# Sheet1.net
KiCad netlist of a schematic drawn in Altium Designer
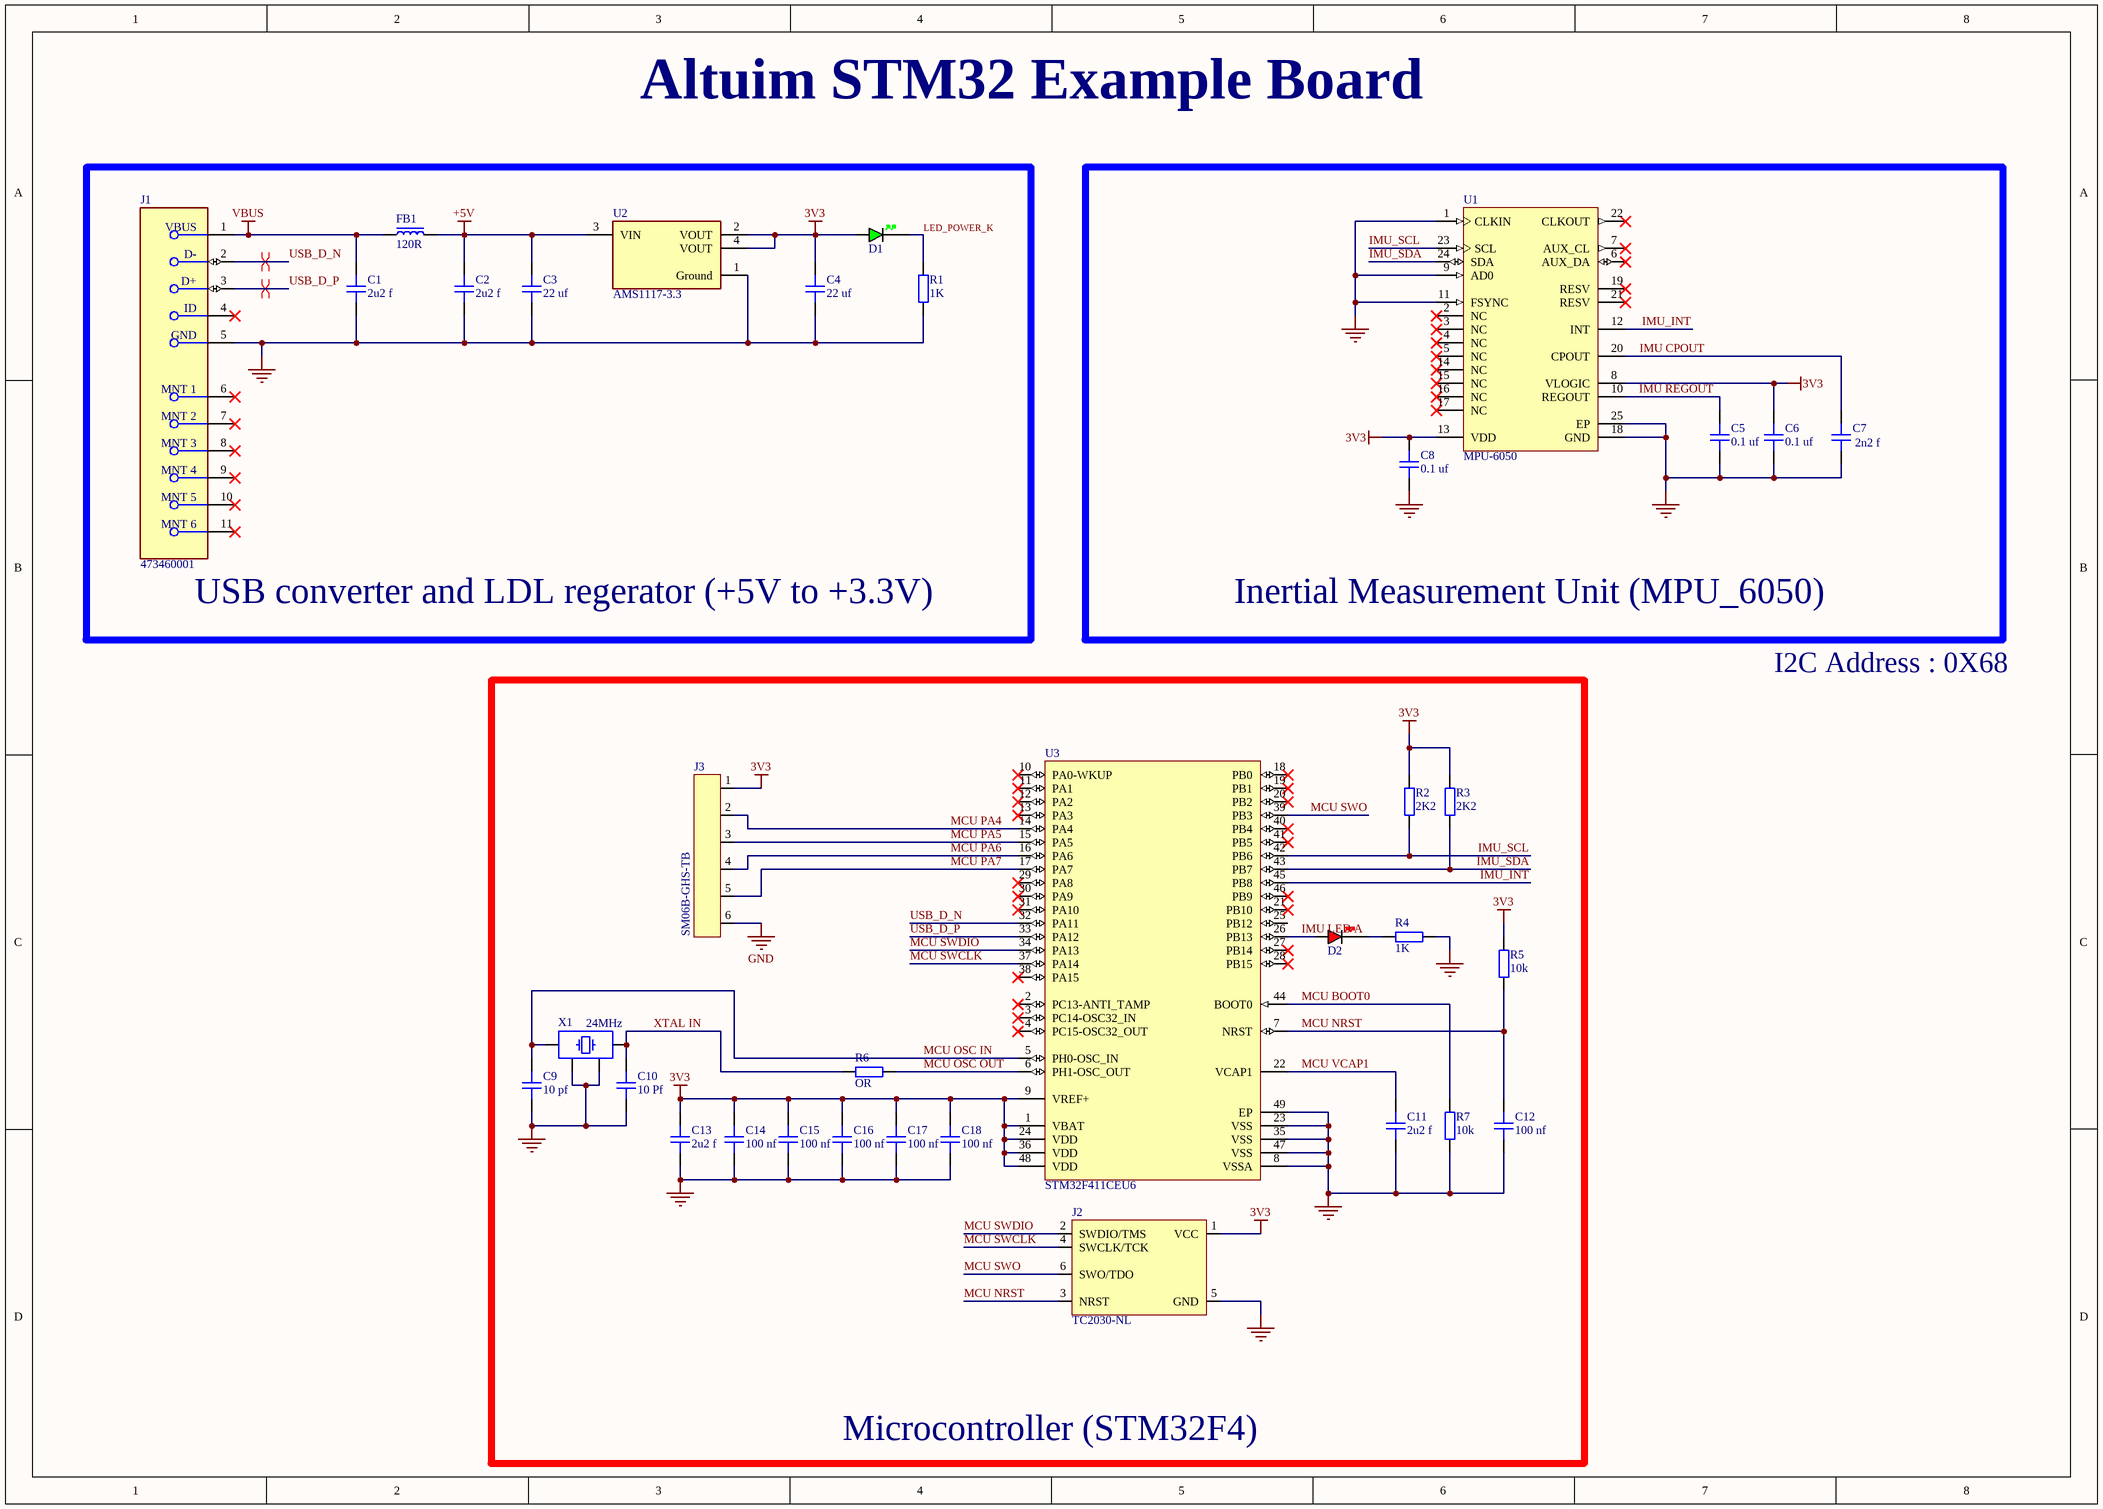
[diagram p0: Sheet1.SchDoc]

(export (version "E")
  (design (tool "Eeschema 10.0.6"))
  (components
    (comp (ref "C1")
      (value "2u2 f")
      (footprint "CAP_0603")
      (description "Capacitor SMD 0603")
      (libsource (lib "Schematic-Lib-PhilsLab") (part "CAP_0603"))
    )
    (comp (ref "C2")
      (value "2u2 f")
      (footprint "CAP_0603")
      (description "Capacitor SMD 0603")
      (libsource (lib "Schematic-Lib-PhilsLab") (part "CAP_0603"))
    )
    (comp (ref "C3")
      (value "22 uf")
      (footprint "CAP_0805")
      (description "Capacitor SMD 0805")
      (libsource (lib "Schematic-Lib-PhilsLab") (part "CAP_0805"))
    )
    (comp (ref "C4")
      (value "22 uf")
      (footprint "CAP_0805")
      (description "Capacitor SMD 0805")
      (libsource (lib "Schematic-Lib-PhilsLab") (part "CAP_0805"))
    )
    (comp (ref "C5")
      (value "0.1 uf")
      (footprint "CAP_0402")
      (description "Capacitor SMD 0402")
      (libsource (lib "Schematic-Lib-PhilsLab") (part "CAP_0402"))
    )
    (comp (ref "C6")
      (value "0.1 uf")
      (footprint "CAP_0402")
      (description "Capacitor SMD 0402")
      (libsource (lib "Schematic-Lib-PhilsLab") (part "CAP_0402"))
    )
    (comp (ref "C7")
      (value "2n2 f")
      (footprint "CAP_0402")
      (description "Capacitor SMD 0402")
      (libsource (lib "Schematic-Lib-PhilsLab") (part "CAP_0402"))
    )
    (comp (ref "C8")
      (value "0.1 uf")
      (footprint "CAP_0402")
      (description "Capacitor SMD 0402")
      (libsource (lib "Schematic-Lib-PhilsLab") (part "CAP_0402"))
    )
    (comp (ref "C9")
      (value "10 pf")
      (footprint "CAP_0402")
      (description "Capacitor SMD 0402")
      (libsource (lib "Schematic-Lib-PhilsLab") (part "CAP_0402"))
    )
    (comp (ref "C10")
      (value "10 Pf")
      (footprint "CAP_0402")
      (description "Capacitor SMD 0402")
      (libsource (lib "Schematic-Lib-PhilsLab") (part "CAP_0402"))
    )
    (comp (ref "C11")
      (value "2u2 f")
      (footprint "CAP_0603")
      (description "Capacitor SMD 0603")
      (libsource (lib "Schematic-Lib-PhilsLab") (part "CAP_0603"))
    )
    (comp (ref "C12")
      (value "100 nf")
      (footprint "CAP_0402")
      (description "Capacitor SMD 0402")
      (libsource (lib "Schematic-Lib-PhilsLab") (part "CAP_0402"))
    )
    (comp (ref "C13")
      (value "2u2 f")
      (footprint "CAP_0603")
      (description "Capacitor SMD 0603")
      (libsource (lib "Schematic-Lib-PhilsLab") (part "CAP_0603"))
    )
    (comp (ref "C14")
      (value "100 nf")
      (footprint "CAP_0402")
      (description "Capacitor SMD 0402")
      (libsource (lib "Schematic-Lib-PhilsLab") (part "CAP_0402"))
    )
    (comp (ref "C15")
      (value "100 nf")
      (footprint "CAP_0402")
      (description "Capacitor SMD 0402")
      (libsource (lib "Schematic-Lib-PhilsLab") (part "CAP_0402"))
    )
    (comp (ref "C16")
      (value "100 nf")
      (footprint "CAP_0402")
      (description "Capacitor SMD 0402")
      (libsource (lib "Schematic-Lib-PhilsLab") (part "CAP_0402"))
    )
    (comp (ref "C17")
      (value "100 nf")
      (footprint "CAP_0402")
      (description "Capacitor SMD 0402")
      (libsource (lib "Schematic-Lib-PhilsLab") (part "CAP_0402"))
    )
    (comp (ref "C18")
      (value "100 nf")
      (footprint "CAP_0402")
      (description "Capacitor SMD 0402")
      (libsource (lib "Schematic-Lib-PhilsLab") (part "CAP_0402"))
    )
    (comp (ref "D1")
      (value "GREEN")
      (footprint "LED_0402_GREEN")
      (description "LED 0402 GREEN SMD")
      (libsource (lib "Schematic-Lib-PhilsLab") (part "LED_0402_GREEN"))
    )
    (comp (ref "D2")
      (value "RED")
      (footprint "LED_0402_RED")
      (description "LED 0402 RED SMD")
      (libsource (lib "Schematic-Lib-PhilsLab") (part "LED_0402_RED"))
    )
    (comp (ref "FB1")
      (value "120R")
      (footprint "FB_0402")
      (description "Ferrite Bead SMD 0402")
      (libsource (lib "Schematic-Lib-PhilsLab") (part "FB_0402"))
    )
    (comp (ref "J1")
      (value "473460001")
      (footprint "FP-473460001-MFG")
      (description "CONN RCPT USB2.0 MICRO B SMD R/A")
      (fields
        (field (name "OCTOPART") "https://octopart.com/47346-0001-molex-7164928")
        (field (name "MANUFACTURER") "Molex")
      )
      (libsource (lib "Altium Content Vault") (part "53ae1f1d9b557310b43ca686e5bb76a"))
    )
    (comp (ref "J2")
      (value "TC2030-NL")
      (footprint "TC2030-NL-FP")
      (description "Tag-Connect No-Solder SWD Debug Connector (No Legs) DO NOT PLACE")
      (fields
        (field (name "MANUFACTURER") "Tag-Connect")
        (field (name "MANUFACTURER PART NUMBER") "TC2030-NL-FP")
      )
      (libsource (lib "Schematic-Lib-PhilsLab") (part "TC2030-NL"))
    )
    (comp (ref "J3")
      (value "SM06B-GHS-TB")
      (footprint "SM06B-GHS-TB")
      (description "Header Connector 6 Position 1.25MM Pitch SMD Horizontal JST GH")
      (fields (field (name "MANUFACTURER") "JST"))
      (libsource (lib "Schematic-Lib-PhilsLab") (part "SM06B-GHS-TB"))
    )
    (comp (ref "R1")
      (value "1K")
      (footprint "RES_0402")
      (description "Resistor SMD 0402")
      (libsource (lib "Schematic-Lib-PhilsLab") (part "RES_0402"))
    )
    (comp (ref "R2")
      (value "2K2")
      (footprint "RES_0402")
      (description "Resistor SMD 0402")
      (libsource (lib "Schematic-Lib-PhilsLab") (part "RES_0402"))
    )
    (comp (ref "R3")
      (value "2K2")
      (footprint "RES_0402")
      (description "Resistor SMD 0402")
      (libsource (lib "Schematic-Lib-PhilsLab") (part "RES_0402"))
    )
    (comp (ref "R4")
      (value "1K")
      (footprint "RES_0402")
      (description "Resistor SMD 0402")
      (libsource (lib "Schematic-Lib-PhilsLab") (part "RES_0402"))
    )
    (comp (ref "R5")
      (value "10k")
      (footprint "RES_0402")
      (description "Resistor SMD 0402")
      (libsource (lib "Schematic-Lib-PhilsLab") (part "RES_0402"))
    )
    (comp (ref "R6")
      (value "OR")
      (footprint "RES_0402")
      (description "Resistor SMD 0402")
      (libsource (lib "Schematic-Lib-PhilsLab") (part "RES_0402"))
    )
    (comp (ref "R7")
      (value "10k")
      (footprint "RES_0402")
      (description "Resistor SMD 0402")
      (libsource (lib "Schematic-Lib-PhilsLab") (part "RES_0402"))
    )
    (comp (ref "U1")
      (value "MPU-6050")
      (footprint "IS-QFN-24_V")
      (fields (field (name "MANUFACTURER") "InvenSense"))
      (libsource (lib "Altium Content Vault") (part "IS-MPU-6050-QFN-24"))
    )
    (comp (ref "U2")
      (value "AMS1117-3.3")
      (footprint "FP-AMS1117-IPC_C")
      (description "LDO Voltage Regulators 1A, 3.3V")
      (fields
        (field (name "OCTOPART") "https://octopart.com/ams1117-3.3-advanced+monolithic+systems-25899300")
        (field (name "MANUFACTURER") "Advanced Monolithic Systems")
      )
      (libsource (lib "Altium Content Vault") (part "8bdbb5f8e77002000e30dd2845d0354"))
    )
    (comp (ref "U3")
      (value "STM32F411CEU6")
      (footprint "STM-UFQFPN48_L")
      (libsource (lib "Altium Content Vault") (part "MC-ARM-STM32F411-UFQFPN48"))
    )
    (comp (ref "X1")
      (value "24MHz")
      (footprint "XTAL_3225")
      (description "Crystal SMD 24MHz 10PPM 7pF 3225")
      (fields
        (field (name "MANUFACTURER") "Epson")
        (field (name "MANUFACTURER PART NUMBER") "TSX-3225 24.0000MF15X-AC")
      )
      (libsource (lib "Schematic-Lib-PhilsLab") (part "TSX-3225_24.0000MF15X-AC"))
    )
  )
  (nets
    (net (code "1") (name "+5V") (class "Default")
      (node (ref "C2") (pin "2") (pinfunction "2_2") (pintype "passive"))
      (node (ref "C3") (pin "2") (pinfunction "2_2") (pintype "passive"))
      (node (ref "FB1") (pin "2") (pinfunction "2_2") (pintype "passive"))
      (node (ref "U2") (pin "3") (pinfunction "VIN_3") (pintype "power_in"))
    )
    (net (code "2") (name "/IMU CPOUT") (class "Default")
      (node (ref "C7") (pin "2") (pinfunction "2_2") (pintype "passive"))
      (node (ref "U1") (pin "20") (pinfunction "CPOUT_20") (pintype "passive"))
    )
    (net (code "3") (name "/IMU LED A") (class "Default")
      (node (ref "D2") (pin "A") (pinfunction "A_A") (pintype "passive"))
      (node (ref "U3") (pin "26") (pinfunction "PB13_26") (pintype "bidirectional"))
    )
    (net (code "4") (name "/IMU REGOUT") (class "Default")
      (node (ref "C5") (pin "1") (pinfunction "1_1") (pintype "passive"))
      (node (ref "U1") (pin "10") (pinfunction "REGOUT_10") (pintype "passive"))
    )
    (net (code "5") (name "/IMU_INT") (class "Default")
      (node (ref "U1") (pin "12") (pinfunction "INT_12") (pintype "open_collector"))
      (node (ref "U3") (pin "45") (pinfunction "PB8_45") (pintype "bidirectional"))
    )
    (net (code "6") (name "/IMU_SCL") (class "Default")
      (node (ref "R2") (pin "1") (pinfunction "1_1") (pintype "passive"))
      (node (ref "U1") (pin "23") (pinfunction "SCL_23") (pintype "input"))
      (node (ref "U3") (pin "42") (pinfunction "PB6_42") (pintype "bidirectional"))
    )
    (net (code "7") (name "/IMU_SDA") (class "Default")
      (node (ref "R3") (pin "1") (pinfunction "1_1") (pintype "passive"))
      (node (ref "U1") (pin "24") (pinfunction "SDA_24") (pintype "bidirectional"))
      (node (ref "U3") (pin "43") (pinfunction "PB7_43") (pintype "bidirectional"))
    )
    (net (code "8") (name "/LED_POWER_K") (class "Default")
      (node (ref "D1") (pin "K") (pinfunction "K_K") (pintype "passive"))
      (node (ref "R1") (pin "2") (pinfunction "2_2") (pintype "passive"))
    )
    (net (code "9") (name "/MCU BOOT0") (class "Default")
      (node (ref "R7") (pin "2") (pinfunction "2_2") (pintype "passive"))
      (node (ref "U3") (pin "44") (pinfunction "BOOT0_44") (pintype "input"))
    )
    (net (code "10") (name "/MCU NRST") (class "Default")
      (node (ref "C12") (pin "2") (pinfunction "2_2") (pintype "passive"))
      (node (ref "J2") (pin "3") (pinfunction "NRST_3") (pintype "passive"))
      (node (ref "R5") (pin "1") (pinfunction "1_1") (pintype "passive"))
      (node (ref "U3") (pin "7") (pinfunction "NRST_7") (pintype "bidirectional"))
    )
    (net (code "11") (name "/MCU OSC IN") (class "Default")
      (node (ref "C9") (pin "2") (pinfunction "2_2") (pintype "passive"))
      (node (ref "U3") (pin "5") (pinfunction "PH0-OSC_IN_5") (pintype "bidirectional"))
      (node (ref "X1") (pin "1") (pinfunction "1_1") (pintype "passive"))
    )
    (net (code "12") (name "/MCU OSC OUT") (class "Default")
      (node (ref "R6") (pin "2") (pinfunction "2_2") (pintype "passive"))
      (node (ref "U3") (pin "6") (pinfunction "PH1-OSC_OUT_6") (pintype "bidirectional"))
    )
    (net (code "13") (name "/MCU PA4") (class "Default")
      (node (ref "J3") (pin "2") (pinfunction "2_2") (pintype "passive"))
      (node (ref "U3") (pin "14") (pinfunction "PA4_14") (pintype "bidirectional"))
    )
    (net (code "14") (name "/MCU PA5") (class "Default")
      (node (ref "J3") (pin "3") (pinfunction "3_3") (pintype "passive"))
      (node (ref "U3") (pin "15") (pinfunction "PA5_15") (pintype "bidirectional"))
    )
    (net (code "15") (name "/MCU PA6") (class "Default")
      (node (ref "J3") (pin "4") (pinfunction "4_4") (pintype "passive"))
      (node (ref "U3") (pin "16") (pinfunction "PA6_16") (pintype "bidirectional"))
    )
    (net (code "16") (name "/MCU PA7") (class "Default")
      (node (ref "J3") (pin "5") (pinfunction "5_5") (pintype "passive"))
      (node (ref "U3") (pin "17") (pinfunction "PA7_17") (pintype "bidirectional"))
    )
    (net (code "17") (name "/MCU SWCLK") (class "Default")
      (node (ref "J2") (pin "4") (pinfunction "SWCLK/TCK_4") (pintype "passive"))
      (node (ref "U3") (pin "37") (pinfunction "PA14_37") (pintype "bidirectional"))
    )
    (net (code "18") (name "/MCU SWDIO") (class "Default")
      (node (ref "J2") (pin "2") (pinfunction "SWDIO/TMS_2") (pintype "passive"))
      (node (ref "U3") (pin "34") (pinfunction "PA13_34") (pintype "bidirectional"))
    )
    (net (code "19") (name "/MCU SWO") (class "Default")
      (node (ref "J2") (pin "6") (pinfunction "SWO/TDO_6") (pintype "passive"))
      (node (ref "U3") (pin "39") (pinfunction "PB3_39") (pintype "bidirectional"))
    )
    (net (code "20") (name "/MCU VCAP1") (class "Default")
      (node (ref "C11") (pin "2") (pinfunction "2_2") (pintype "passive"))
      (node (ref "U3") (pin "22") (pinfunction "VCAP1_22") (pintype "passive"))
    )
    (net (code "21") (name "/USB_D_N") (class "Default")
      (node (ref "J1") (pin "2") (pinfunction "D-_2") (pintype "bidirectional"))
      (node (ref "U3") (pin "32") (pinfunction "PA11_32") (pintype "bidirectional"))
    )
    (net (code "22") (name "/USB_D_P") (class "Default")
      (node (ref "J1") (pin "3") (pinfunction "D+_3") (pintype "bidirectional"))
      (node (ref "U3") (pin "33") (pinfunction "PA12_33") (pintype "bidirectional"))
    )
    (net (code "23") (name "/XTAL IN") (class "Default")
      (node (ref "C10") (pin "2") (pinfunction "2_2") (pintype "passive"))
      (node (ref "R6") (pin "1") (pinfunction "1_1") (pintype "passive"))
      (node (ref "X1") (pin "3") (pinfunction "3_3") (pintype "passive"))
    )
    (net (code "24") (name "3V3") (class "Default")
      (node (ref "C13") (pin "2") (pinfunction "2_2") (pintype "passive"))
      (node (ref "C14") (pin "2") (pinfunction "2_2") (pintype "passive"))
      (node (ref "C15") (pin "2") (pinfunction "2_2") (pintype "passive"))
      (node (ref "C16") (pin "2") (pinfunction "2_2") (pintype "passive"))
      (node (ref "C17") (pin "2") (pinfunction "2_2") (pintype "passive"))
      (node (ref "C18") (pin "2") (pinfunction "2_2") (pintype "passive"))
      (node (ref "C4") (pin "2") (pinfunction "2_2") (pintype "passive"))
      (node (ref "C6") (pin "1") (pinfunction "1_1") (pintype "passive"))
      (node (ref "C8") (pin "2") (pinfunction "2_2") (pintype "passive"))
      (node (ref "D1") (pin "A") (pinfunction "A_A") (pintype "passive"))
      (node (ref "J2") (pin "1") (pinfunction "VCC_1") (pintype "passive"))
      (node (ref "J3") (pin "1") (pinfunction "1_1") (pintype "passive"))
      (node (ref "R2") (pin "2") (pinfunction "2_2") (pintype "passive"))
      (node (ref "R3") (pin "2") (pinfunction "2_2") (pintype "passive"))
      (node (ref "R5") (pin "2") (pinfunction "2_2") (pintype "passive"))
      (node (ref "U1") (pin "13") (pinfunction "VDD_13") (pintype "power_in"))
      (node (ref "U1") (pin "8") (pinfunction "VLOGIC_8") (pintype "power_in"))
      (node (ref "U2") (pin "2") (pinfunction "VOUT_2") (pintype "passive"))
      (node (ref "U2") (pin "4") (pinfunction "VOUT_4") (pintype "passive"))
      (node (ref "U3") (pin "1") (pinfunction "VBAT_1") (pintype "power_in"))
      (node (ref "U3") (pin "24") (pinfunction "VDD_24") (pintype "power_in"))
      (node (ref "U3") (pin "36") (pinfunction "VDD_36") (pintype "power_in"))
      (node (ref "U3") (pin "48") (pinfunction "VDD_48") (pintype "power_in"))
      (node (ref "U3") (pin "9") (pinfunction "VREF+_9") (pintype "power_in"))
    )
    (net (code "25") (name "GND") (class "Default")
      (node (ref "C1") (pin "1") (pinfunction "1_1") (pintype "passive"))
      (node (ref "C10") (pin "1") (pinfunction "1_1") (pintype "passive"))
      (node (ref "C11") (pin "1") (pinfunction "1_1") (pintype "passive"))
      (node (ref "C12") (pin "1") (pinfunction "1_1") (pintype "passive"))
      (node (ref "C13") (pin "1") (pinfunction "1_1") (pintype "passive"))
      (node (ref "C14") (pin "1") (pinfunction "1_1") (pintype "passive"))
      (node (ref "C15") (pin "1") (pinfunction "1_1") (pintype "passive"))
      (node (ref "C16") (pin "1") (pinfunction "1_1") (pintype "passive"))
      (node (ref "C17") (pin "1") (pinfunction "1_1") (pintype "passive"))
      (node (ref "C18") (pin "1") (pinfunction "1_1") (pintype "passive"))
      (node (ref "C2") (pin "1") (pinfunction "1_1") (pintype "passive"))
      (node (ref "C3") (pin "1") (pinfunction "1_1") (pintype "passive"))
      (node (ref "C4") (pin "1") (pinfunction "1_1") (pintype "passive"))
      (node (ref "C5") (pin "2") (pinfunction "2_2") (pintype "passive"))
      (node (ref "C6") (pin "2") (pinfunction "2_2") (pintype "passive"))
      (node (ref "C7") (pin "1") (pinfunction "1_1") (pintype "passive"))
      (node (ref "C8") (pin "1") (pinfunction "1_1") (pintype "passive"))
      (node (ref "C9") (pin "1") (pinfunction "1_1") (pintype "passive"))
      (node (ref "J1") (pin "5") (pinfunction "GND_5") (pintype "power_in"))
      (node (ref "J2") (pin "5") (pinfunction "GND_5") (pintype "passive"))
      (node (ref "J3") (pin "6") (pinfunction "6_6") (pintype "passive"))
      (node (ref "R1") (pin "1") (pinfunction "1_1") (pintype "passive"))
      (node (ref "R4") (pin "1") (pinfunction "1_1") (pintype "passive"))
      (node (ref "R7") (pin "1") (pinfunction "1_1") (pintype "passive"))
      (node (ref "U1") (pin "1") (pinfunction "CLKIN_1") (pintype "input"))
      (node (ref "U1") (pin "11") (pinfunction "FSYNC_11") (pintype "input"))
      (node (ref "U1") (pin "18") (pinfunction "GND_18") (pintype "power_in"))
      (node (ref "U1") (pin "25") (pinfunction "EP_25") (pintype "power_in"))
      (node (ref "U1") (pin "9") (pinfunction "AD0_9") (pintype "input"))
      (node (ref "U2") (pin "1") (pinfunction "Ground_1") (pintype "power_in"))
      (node (ref "U3") (pin "23") (pinfunction "VSS_23") (pintype "power_in"))
      (node (ref "U3") (pin "35") (pinfunction "VSS_35") (pintype "power_in"))
      (node (ref "U3") (pin "47") (pinfunction "VSS_47") (pintype "power_in"))
      (node (ref "U3") (pin "49") (pinfunction "EP_49") (pintype "power_in"))
      (node (ref "U3") (pin "8") (pinfunction "VSSA_8") (pintype "power_in"))
      (node (ref "X1") (pin "2") (pinfunction "2_2") (pintype "passive"))
      (node (ref "X1") (pin "4") (pinfunction "4_4") (pintype "passive"))
    )
    (net (code "26") (name "Net-(D2-PadK)") (class "Default")
      (node (ref "D2") (pin "K") (pinfunction "K_K") (pintype "passive"))
      (node (ref "R4") (pin "2") (pinfunction "2_2") (pintype "passive"))
    )
    (net (code "27") (name "VBUS") (class "Default")
      (node (ref "C1") (pin "2") (pinfunction "2_2") (pintype "passive"))
      (node (ref "FB1") (pin "1") (pinfunction "1_1") (pintype "passive"))
      (node (ref "J1") (pin "1") (pinfunction "VBUS_1") (pintype "power_in"))
    )
    (net (code "28") (name "unconnected-(J1-ID-Pad4)") (class "Default")
      (node (ref "J1") (pin "4") (pinfunction "ID_4") (pintype "passive+no_connect"))
    )
    (net (code "29") (name "unconnected-(J1-MNT_1-Pad6)") (class "Default")
      (node (ref "J1") (pin "6") (pinfunction "MNT_1_6") (pintype "passive+no_connect"))
    )
    (net (code "30") (name "unconnected-(J1-MNT_2-Pad7)") (class "Default")
      (node (ref "J1") (pin "7") (pinfunction "MNT_2_7") (pintype "passive+no_connect"))
    )
    (net (code "31") (name "unconnected-(J1-MNT_3-Pad8)") (class "Default")
      (node (ref "J1") (pin "8") (pinfunction "MNT_3_8") (pintype "passive+no_connect"))
    )
    (net (code "32") (name "unconnected-(J1-MNT_4-Pad9)") (class "Default")
      (node (ref "J1") (pin "9") (pinfunction "MNT_4_9") (pintype "passive+no_connect"))
    )
    (net (code "33") (name "unconnected-(J1-MNT_5-Pad10)") (class "Default")
      (node (ref "J1") (pin "10") (pinfunction "MNT_5_10") (pintype "passive+no_connect"))
    )
    (net (code "34") (name "unconnected-(J1-MNT_6-Pad11)") (class "Default")
      (node (ref "J1") (pin "11") (pinfunction "MNT_6_11") (pintype "passive+no_connect"))
    )
    (net (code "35") (name "unconnected-(U1-AUX_CL-Pad7)") (class "Default")
      (node (ref "U1") (pin "7") (pinfunction "AUX_CL_7") (pintype "output+no_connect"))
    )
    (net (code "36") (name "unconnected-(U1-AUX_DA-Pad6)") (class "Default")
      (node (ref "U1") (pin "6") (pinfunction "AUX_DA_6") (pintype "bidirectional+no_connect"))
    )
    (net (code "37") (name "unconnected-(U1-CLKOUT-Pad22)") (class "Default")
      (node (ref "U1") (pin "22") (pinfunction "CLKOUT_22") (pintype "output+no_connect"))
    )
    (net (code "38") (name "unconnected-(U1-NC-Pad2)") (class "Default")
      (node (ref "U1") (pin "2") (pinfunction "NC_2") (pintype "passive+no_connect"))
    )
    (net (code "39") (name "unconnected-(U1-NC-Pad3)") (class "Default")
      (node (ref "U1") (pin "3") (pinfunction "NC_3") (pintype "passive+no_connect"))
    )
    (net (code "40") (name "unconnected-(U1-NC-Pad4)") (class "Default")
      (node (ref "U1") (pin "4") (pinfunction "NC_4") (pintype "passive+no_connect"))
    )
    (net (code "41") (name "unconnected-(U1-NC-Pad5)") (class "Default")
      (node (ref "U1") (pin "5") (pinfunction "NC_5") (pintype "passive+no_connect"))
    )
    (net (code "42") (name "unconnected-(U1-NC-Pad14)") (class "Default")
      (node (ref "U1") (pin "14") (pinfunction "NC_14") (pintype "passive+no_connect"))
    )
    (net (code "43") (name "unconnected-(U1-NC-Pad15)") (class "Default")
      (node (ref "U1") (pin "15") (pinfunction "NC_15") (pintype "passive+no_connect"))
    )
    (net (code "44") (name "unconnected-(U1-NC-Pad16)") (class "Default")
      (node (ref "U1") (pin "16") (pinfunction "NC_16") (pintype "passive+no_connect"))
    )
    (net (code "45") (name "unconnected-(U1-NC-Pad17)") (class "Default")
      (node (ref "U1") (pin "17") (pinfunction "NC_17") (pintype "passive+no_connect"))
    )
    (net (code "46") (name "unconnected-(U1-RESV-Pad19)") (class "Default")
      (node (ref "U1") (pin "19") (pinfunction "RESV_19") (pintype "passive+no_connect"))
    )
    (net (code "47") (name "unconnected-(U1-RESV-Pad21)") (class "Default")
      (node (ref "U1") (pin "21") (pinfunction "RESV_21") (pintype "passive+no_connect"))
    )
    (net (code "48") (name "unconnected-(U3-PA0-WKUP-Pad10)") (class "Default")
      (node (ref "U3") (pin "10") (pinfunction "PA0-WKUP_10") (pintype "bidirectional+no_connect"))
    )
    (net (code "49") (name "unconnected-(U3-PA1-Pad11)") (class "Default")
      (node (ref "U3") (pin "11") (pinfunction "PA1_11") (pintype "bidirectional+no_connect"))
    )
    (net (code "50") (name "unconnected-(U3-PA2-Pad12)") (class "Default")
      (node (ref "U3") (pin "12") (pinfunction "PA2_12") (pintype "bidirectional+no_connect"))
    )
    (net (code "51") (name "unconnected-(U3-PA3-Pad13)") (class "Default")
      (node (ref "U3") (pin "13") (pinfunction "PA3_13") (pintype "bidirectional+no_connect"))
    )
    (net (code "52") (name "unconnected-(U3-PA8-Pad29)") (class "Default")
      (node (ref "U3") (pin "29") (pinfunction "PA8_29") (pintype "bidirectional+no_connect"))
    )
    (net (code "53") (name "unconnected-(U3-PA9-Pad30)") (class "Default")
      (node (ref "U3") (pin "30") (pinfunction "PA9_30") (pintype "bidirectional+no_connect"))
    )
    (net (code "54") (name "unconnected-(U3-PA10-Pad31)") (class "Default")
      (node (ref "U3") (pin "31") (pinfunction "PA10_31") (pintype "bidirectional+no_connect"))
    )
    (net (code "55") (name "unconnected-(U3-PA15-Pad38)") (class "Default")
      (node (ref "U3") (pin "38") (pinfunction "PA15_38") (pintype "bidirectional+no_connect"))
    )
    (net (code "56") (name "unconnected-(U3-PB0-Pad18)") (class "Default")
      (node (ref "U3") (pin "18") (pinfunction "PB0_18") (pintype "bidirectional+no_connect"))
    )
    (net (code "57") (name "unconnected-(U3-PB1-Pad19)") (class "Default")
      (node (ref "U3") (pin "19") (pinfunction "PB1_19") (pintype "bidirectional+no_connect"))
    )
    (net (code "58") (name "unconnected-(U3-PB2-Pad20)") (class "Default")
      (node (ref "U3") (pin "20") (pinfunction "PB2_20") (pintype "bidirectional+no_connect"))
    )
    (net (code "59") (name "unconnected-(U3-PB4-Pad40)") (class "Default")
      (node (ref "U3") (pin "40") (pinfunction "PB4_40") (pintype "bidirectional+no_connect"))
    )
    (net (code "60") (name "unconnected-(U3-PB5-Pad41)") (class "Default")
      (node (ref "U3") (pin "41") (pinfunction "PB5_41") (pintype "bidirectional+no_connect"))
    )
    (net (code "61") (name "unconnected-(U3-PB9-Pad46)") (class "Default")
      (node (ref "U3") (pin "46") (pinfunction "PB9_46") (pintype "bidirectional+no_connect"))
    )
    (net (code "62") (name "unconnected-(U3-PB10-Pad21)") (class "Default")
      (node (ref "U3") (pin "21") (pinfunction "PB10_21") (pintype "bidirectional+no_connect"))
    )
    (net (code "63") (name "unconnected-(U3-PB12-Pad25)") (class "Default")
      (node (ref "U3") (pin "25") (pinfunction "PB12_25") (pintype "bidirectional"))
    )
    (net (code "64") (name "unconnected-(U3-PB14-Pad27)") (class "Default")
      (node (ref "U3") (pin "27") (pinfunction "PB14_27") (pintype "bidirectional+no_connect"))
    )
    (net (code "65") (name "unconnected-(U3-PB15-Pad28)") (class "Default")
      (node (ref "U3") (pin "28") (pinfunction "PB15_28") (pintype "bidirectional+no_connect"))
    )
    (net (code "66") (name "unconnected-(U3-PC13-ANTI_TAMP-Pad2)") (class "Default")
      (node (ref "U3") (pin "2") (pinfunction "PC13-ANTI_TAMP_2") (pintype "bidirectional+no_connect"))
    )
    (net (code "67") (name "unconnected-(U3-PC14-OSC32_IN-Pad3)") (class "Default")
      (node (ref "U3") (pin "3") (pinfunction "PC14-OSC32_IN_3") (pintype "bidirectional+no_connect"))
    )
    (net (code "68") (name "unconnected-(U3-PC15-OSC32_OUT-Pad4)") (class "Default")
      (node (ref "U3") (pin "4") (pinfunction "PC15-OSC32_OUT_4") (pintype "bidirectional+no_connect"))
    )
  )
)
